# untitled.net
KiCad netlist of a schematic drawn in EAGLE
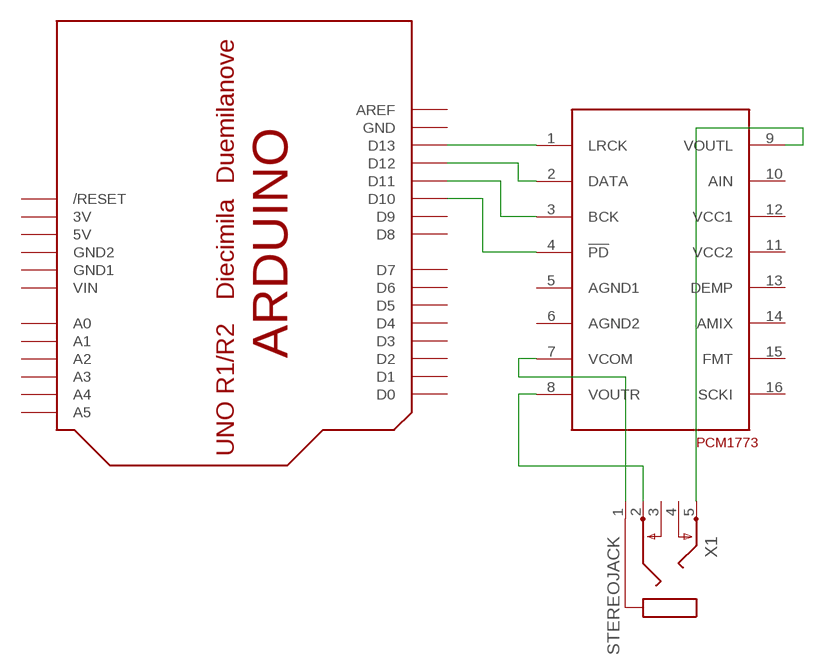
[diagram p0: schematic, sheet 1]

(export (version "E")
  (design (tool "Eeschema 10.0.6"))
  (components
    (comp (ref "U$1")
      (value "ARDUINO-NOHOLE")
      (footprint "eagle-import:ARDUINO-NOHOLE")
      (libsource (lib "eagle-import") (part "ARDUINO-NOHOLE"))
    )
    (comp (ref "U$2")
      (value "PCM1773")
      (footprint "eagle-import:TSSOP16")
      (libsource (lib "eagle-import") (part "PCM1773"))
    )
    (comp (ref "X1")
      (value "STEREOJACK")
      (footprint "eagle-import:STX3100")
      (libsource (lib "eagle-import") (part "STEREOJACK"))
    )
  )
  (nets
    (net (code "1") (name "/3V") (class "Default")
      (node (ref "U$1") (pin "3V") (pinfunction "3V_3V") (pintype "power_in"))
    )
    (net (code "2") (name "/5V") (class "Default")
      (node (ref "U$1") (pin "5V") (pinfunction "5V_5V") (pintype "power_in"))
    )
    (net (code "3") (name "/AGND1") (class "Default")
      (node (ref "U$2") (pin "5") (pinfunction "AGND1_5") (pintype "power_in"))
    )
    (net (code "4") (name "/AGND2") (class "Default")
      (node (ref "U$2") (pin "6") (pinfunction "AGND2_6") (pintype "power_in"))
    )
    (net (code "5") (name "/GND") (class "Default")
      (node (ref "U$1") (pin "GND") (pinfunction "GND_GND") (pintype "power_in"))
    )
    (net (code "6") (name "/GND1") (class "Default")
      (node (ref "U$1") (pin "GND1") (pinfunction "GND1_GND1") (pintype "power_in"))
    )
    (net (code "7") (name "/GND2") (class "Default")
      (node (ref "U$1") (pin "GND2") (pinfunction "GND2_GND2") (pintype "power_in"))
    )
    (net (code "8") (name "/VCC1") (class "Default")
      (node (ref "U$2") (pin "12") (pinfunction "VCC1_12") (pintype "power_in"))
    )
    (net (code "9") (name "/VCC2") (class "Default")
      (node (ref "U$2") (pin "11") (pinfunction "VCC2_11") (pintype "power_in"))
    )
    (net (code "10") (name "/VIN") (class "Default")
      (node (ref "U$1") (pin "VIN") (pinfunction "VIN_VIN") (pintype "power_in"))
    )
    (net (code "11") (name "Net-(U$2-BCK)") (class "Default")
      (node (ref "U$1") (pin "D11") (pinfunction "D11_D11") (pintype "bidirectional"))
      (node (ref "U$2") (pin "3") (pinfunction "BCK_3") (pintype "bidirectional"))
    )
    (net (code "12") (name "Net-(U$2-DATA)") (class "Default")
      (node (ref "U$1") (pin "D12") (pinfunction "D12_D12") (pintype "bidirectional"))
      (node (ref "U$2") (pin "2") (pinfunction "DATA_2") (pintype "bidirectional"))
    )
    (net (code "13") (name "Net-(U$2-LRCK)") (class "Default")
      (node (ref "U$1") (pin "D13") (pinfunction "D13_D13") (pintype "bidirectional"))
      (node (ref "U$2") (pin "1") (pinfunction "LRCK_1") (pintype "bidirectional"))
    )
    (net (code "14") (name "Net-(U$2-VCOM)") (class "Default")
      (node (ref "U$2") (pin "7") (pinfunction "VCOM_7") (pintype "power_in"))
      (node (ref "X1") (pin "1") (pinfunction "1_1") (pintype "passive"))
    )
    (net (code "15") (name "Net-(U$2-VOUTL)") (class "Default")
      (node (ref "U$2") (pin "9") (pinfunction "VOUTL_9") (pintype "bidirectional"))
      (node (ref "X1") (pin "5") (pinfunction "5_5") (pintype "passive"))
    )
    (net (code "16") (name "Net-(U$2-VOUTR)") (class "Default")
      (node (ref "U$2") (pin "8") (pinfunction "VOUTR_8") (pintype "bidirectional"))
      (node (ref "X1") (pin "2") (pinfunction "2_2") (pintype "passive"))
    )
    (net (code "17") (name "Net-(U$2-~{PD})") (class "Default")
      (node (ref "U$1") (pin "D10") (pinfunction "D10_D10") (pintype "bidirectional"))
      (node (ref "U$2") (pin "4") (pinfunction "~{PD}_4") (pintype "bidirectional"))
    )
    (net (code "18") (name "unconnected-(U$1-PadA0)") (class "Default")
      (node (ref "U$1") (pin "A0") (pinfunction "A0_A0") (pintype "bidirectional"))
    )
    (net (code "19") (name "unconnected-(U$1-PadA1)") (class "Default")
      (node (ref "U$1") (pin "A1") (pinfunction "A1_A1") (pintype "bidirectional"))
    )
    (net (code "20") (name "unconnected-(U$1-PadA2)") (class "Default")
      (node (ref "U$1") (pin "A2") (pinfunction "A2_A2") (pintype "bidirectional"))
    )
    (net (code "21") (name "unconnected-(U$1-PadA3)") (class "Default")
      (node (ref "U$1") (pin "A3") (pinfunction "A3_A3") (pintype "bidirectional"))
    )
    (net (code "22") (name "unconnected-(U$1-PadA4)") (class "Default")
      (node (ref "U$1") (pin "A4") (pinfunction "A4_A4") (pintype "bidirectional"))
    )
    (net (code "23") (name "unconnected-(U$1-PadA5)") (class "Default")
      (node (ref "U$1") (pin "A5") (pinfunction "A5_A5") (pintype "bidirectional"))
    )
    (net (code "24") (name "unconnected-(U$1-PadAREF)") (class "Default")
      (node (ref "U$1") (pin "AREF") (pinfunction "AREF_AREF") (pintype "bidirectional"))
    )
    (net (code "25") (name "unconnected-(U$1-PadD0)") (class "Default")
      (node (ref "U$1") (pin "D0") (pinfunction "D0_D0") (pintype "bidirectional"))
    )
    (net (code "26") (name "unconnected-(U$1-PadD1)") (class "Default")
      (node (ref "U$1") (pin "D1") (pinfunction "D1_D1") (pintype "bidirectional"))
    )
    (net (code "27") (name "unconnected-(U$1-PadD2)") (class "Default")
      (node (ref "U$1") (pin "D2") (pinfunction "D2_D2") (pintype "bidirectional"))
    )
    (net (code "28") (name "unconnected-(U$1-PadD3)") (class "Default")
      (node (ref "U$1") (pin "D3") (pinfunction "D3_D3") (pintype "bidirectional"))
    )
    (net (code "29") (name "unconnected-(U$1-PadD4)") (class "Default")
      (node (ref "U$1") (pin "D4") (pinfunction "D4_D4") (pintype "bidirectional"))
    )
    (net (code "30") (name "unconnected-(U$1-PadD5)") (class "Default")
      (node (ref "U$1") (pin "D5") (pinfunction "D5_D5") (pintype "bidirectional"))
    )
    (net (code "31") (name "unconnected-(U$1-PadD6)") (class "Default")
      (node (ref "U$1") (pin "D6") (pinfunction "D6_D6") (pintype "bidirectional"))
    )
    (net (code "32") (name "unconnected-(U$1-PadD7)") (class "Default")
      (node (ref "U$1") (pin "D7") (pinfunction "D7_D7") (pintype "bidirectional"))
    )
    (net (code "33") (name "unconnected-(U$1-PadD8)") (class "Default")
      (node (ref "U$1") (pin "D8") (pinfunction "D8_D8") (pintype "bidirectional"))
    )
    (net (code "34") (name "unconnected-(U$1-PadD9)") (class "Default")
      (node (ref "U$1") (pin "D9") (pinfunction "D9_D9") (pintype "bidirectional"))
    )
    (net (code "35") (name "unconnected-(U$1-{slash}RESET-PadRESET)") (class "Default")
      (node (ref "U$1") (pin "RESET") (pinfunction "/RESET_RESET") (pintype "bidirectional"))
    )
    (net (code "36") (name "unconnected-(U$2-AIN-Pad10)") (class "Default")
      (node (ref "U$2") (pin "10") (pinfunction "AIN_10") (pintype "bidirectional"))
    )
    (net (code "37") (name "unconnected-(U$2-AMIX-Pad14)") (class "Default")
      (node (ref "U$2") (pin "14") (pinfunction "AMIX_14") (pintype "bidirectional"))
    )
    (net (code "38") (name "unconnected-(U$2-DEMP-Pad13)") (class "Default")
      (node (ref "U$2") (pin "13") (pinfunction "DEMP_13") (pintype "bidirectional"))
    )
    (net (code "39") (name "unconnected-(U$2-FMT-Pad15)") (class "Default")
      (node (ref "U$2") (pin "15") (pinfunction "FMT_15") (pintype "bidirectional"))
    )
    (net (code "40") (name "unconnected-(U$2-SCKI-Pad16)") (class "Default")
      (node (ref "U$2") (pin "16") (pinfunction "SCKI_16") (pintype "bidirectional"))
    )
    (net (code "41") (name "unconnected-(X1-Pad3)") (class "Default")
      (node (ref "X1") (pin "3") (pinfunction "3_3") (pintype "passive"))
    )
    (net (code "42") (name "unconnected-(X1-Pad4)") (class "Default")
      (node (ref "X1") (pin "4") (pinfunction "4_4") (pintype "passive"))
    )
  )
)
